# DC-DC_SY8029AIC.net
KiCad netlist of a schematic drawn in Altium Designer
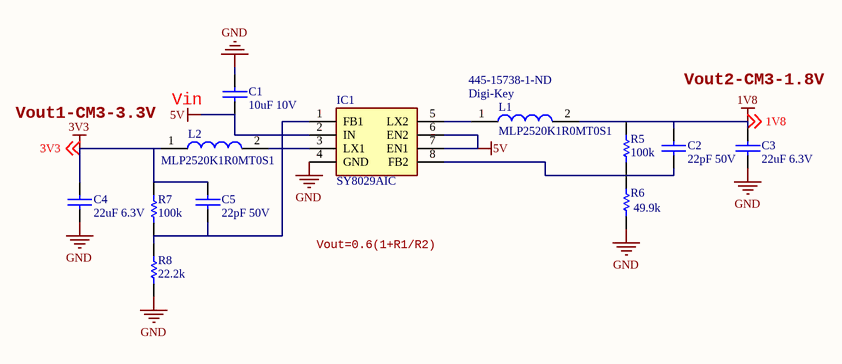
[diagram p0: DC-DC SY8029AIC.SchDoc]

(export (version "E")
  (design (tool "Eeschema 10.0.6"))
  (components
    (comp (ref "C1") (value "10uF 10V") (footprint "0805C") (libsource (lib "电容") (part "CAP-NP")))
    (comp (ref "C2") (value "22pF 50V") (footprint "0402C") (libsource (lib "电容") (part "CAP-NP")))
    (comp (ref "C3") (value "22uF 6.3V") (footprint "0603C") (libsource (lib "电容") (part "CAP-NP")))
    (comp (ref "C4") (value "22uF 6.3V") (footprint "0603C") (libsource (lib "电容") (part "CAP-NP")))
    (comp (ref "C5") (value "22pF 50V") (footprint "0402C") (libsource (lib "电容") (part "CAP-NP")))
    (comp (ref "IC1")
      (value "SY8029AIC")
      (footprint "SamacSys:SOT65P280X110-8N")
      (description "Integrated Circuit")
      (libsource (lib "*") (part "SY8029AIC"))
    )
    (comp (ref "L1")
      (value "MLP2520K1R0MT0S1")
      (footprint "SamacSys:INDC2520X100N")
      (description "Inductor")
      (fields
        (field (name "MOUSER PART NUMBER") "810-MLP2520K1R0MT0S1")
        (field (name "SUPPLIER 1") "Digi-Key")
        (field (name "SUPPLIER PART NUMBER 1") "445-15738-1-ND")
      )
      (libsource (lib "*") (part "MLP2520K1R0MT0S1"))
    )
    (comp (ref "L2")
      (value "MLP2520K1R0MT0S1")
      (footprint "SamacSys:INDC2520X100N")
      (description "Inductor")
      (fields (field (name "MOUSER PART NUMBER") "810-MLP2520K1R0MT0S1"))
      (libsource (lib "*") (part "MLP2520K1R0MT0S1"))
    )
    (comp (ref "R5") (value "100k") (footprint "0402R") (libsource (lib "电阻") (part "RES")))
    (comp (ref "R6") (value "49.9k") (footprint "0402R") (libsource (lib "电阻") (part "RES")))
    (comp (ref "R7") (value "100k") (footprint "0402R") (libsource (lib "电阻") (part "RES")))
    (comp (ref "R8") (value "22.2k") (footprint "0402R") (libsource (lib "电阻") (part "RES")))
  )
  (nets
    (net (code "1") (name "1V8") (class "Default")
      (node (ref "C2") (pin "2") (pinfunction "2_2") (pintype "passive"))
      (node (ref "C3") (pin "2") (pinfunction "2_2") (pintype "passive"))
      (node (ref "L1") (pin "2") (pinfunction "2_2") (pintype "passive"))
      (node (ref "R5") (pin "2") (pinfunction "2_2") (pintype "passive"))
    )
    (net (code "2") (name "3V3") (class "Default")
      (node (ref "C4") (pin "2") (pinfunction "2_2") (pintype "passive"))
      (node (ref "C5") (pin "2") (pinfunction "2_2") (pintype "passive"))
      (node (ref "L2") (pin "1") (pinfunction "1_1") (pintype "passive"))
      (node (ref "R7") (pin "2") (pinfunction "2_2") (pintype "passive"))
    )
    (net (code "3") (name "5V") (class "Default")
      (node (ref "C1") (pin "1") (pinfunction "1_1") (pintype "passive"))
      (node (ref "IC1") (pin "2") (pinfunction "IN_2") (pintype "passive"))
      (node (ref "IC1") (pin "6") (pinfunction "EN2_6") (pintype "passive"))
      (node (ref "IC1") (pin "7") (pinfunction "EN1_7") (pintype "passive"))
    )
    (net (code "4") (name "GND") (class "Default")
      (node (ref "C1") (pin "2") (pinfunction "2_2") (pintype "passive"))
      (node (ref "C3") (pin "1") (pinfunction "1_1") (pintype "passive"))
      (node (ref "C4") (pin "1") (pinfunction "1_1") (pintype "passive"))
      (node (ref "IC1") (pin "4") (pinfunction "GND_4") (pintype "passive"))
      (node (ref "R6") (pin "1") (pinfunction "1_1") (pintype "passive"))
      (node (ref "R8") (pin "1") (pinfunction "1_1") (pintype "passive"))
    )
    (net (code "5") (name "Net-(IC1-FB1)") (class "Default")
      (node (ref "C5") (pin "1") (pinfunction "1_1") (pintype "passive"))
      (node (ref "IC1") (pin "1") (pinfunction "FB1_1") (pintype "passive"))
      (node (ref "R7") (pin "1") (pinfunction "1_1") (pintype "passive"))
      (node (ref "R8") (pin "2") (pinfunction "2_2") (pintype "passive"))
    )
    (net (code "6") (name "Net-(IC1-FB2)") (class "Default")
      (node (ref "C2") (pin "1") (pinfunction "1_1") (pintype "passive"))
      (node (ref "IC1") (pin "8") (pinfunction "FB2_8") (pintype "passive"))
      (node (ref "R5") (pin "1") (pinfunction "1_1") (pintype "passive"))
      (node (ref "R6") (pin "2") (pinfunction "2_2") (pintype "passive"))
    )
    (net (code "7") (name "Net-(IC1-LX1)") (class "Default")
      (node (ref "IC1") (pin "3") (pinfunction "LX1_3") (pintype "passive"))
      (node (ref "L2") (pin "2") (pinfunction "2_2") (pintype "passive"))
    )
    (net (code "8") (name "Net-(IC1-LX2)") (class "Default")
      (node (ref "IC1") (pin "5") (pinfunction "LX2_5") (pintype "passive"))
      (node (ref "L1") (pin "1") (pinfunction "1_1") (pintype "passive"))
    )
  )
)
